# Sheet2.net
KiCad netlist of a schematic drawn in Altium Designer
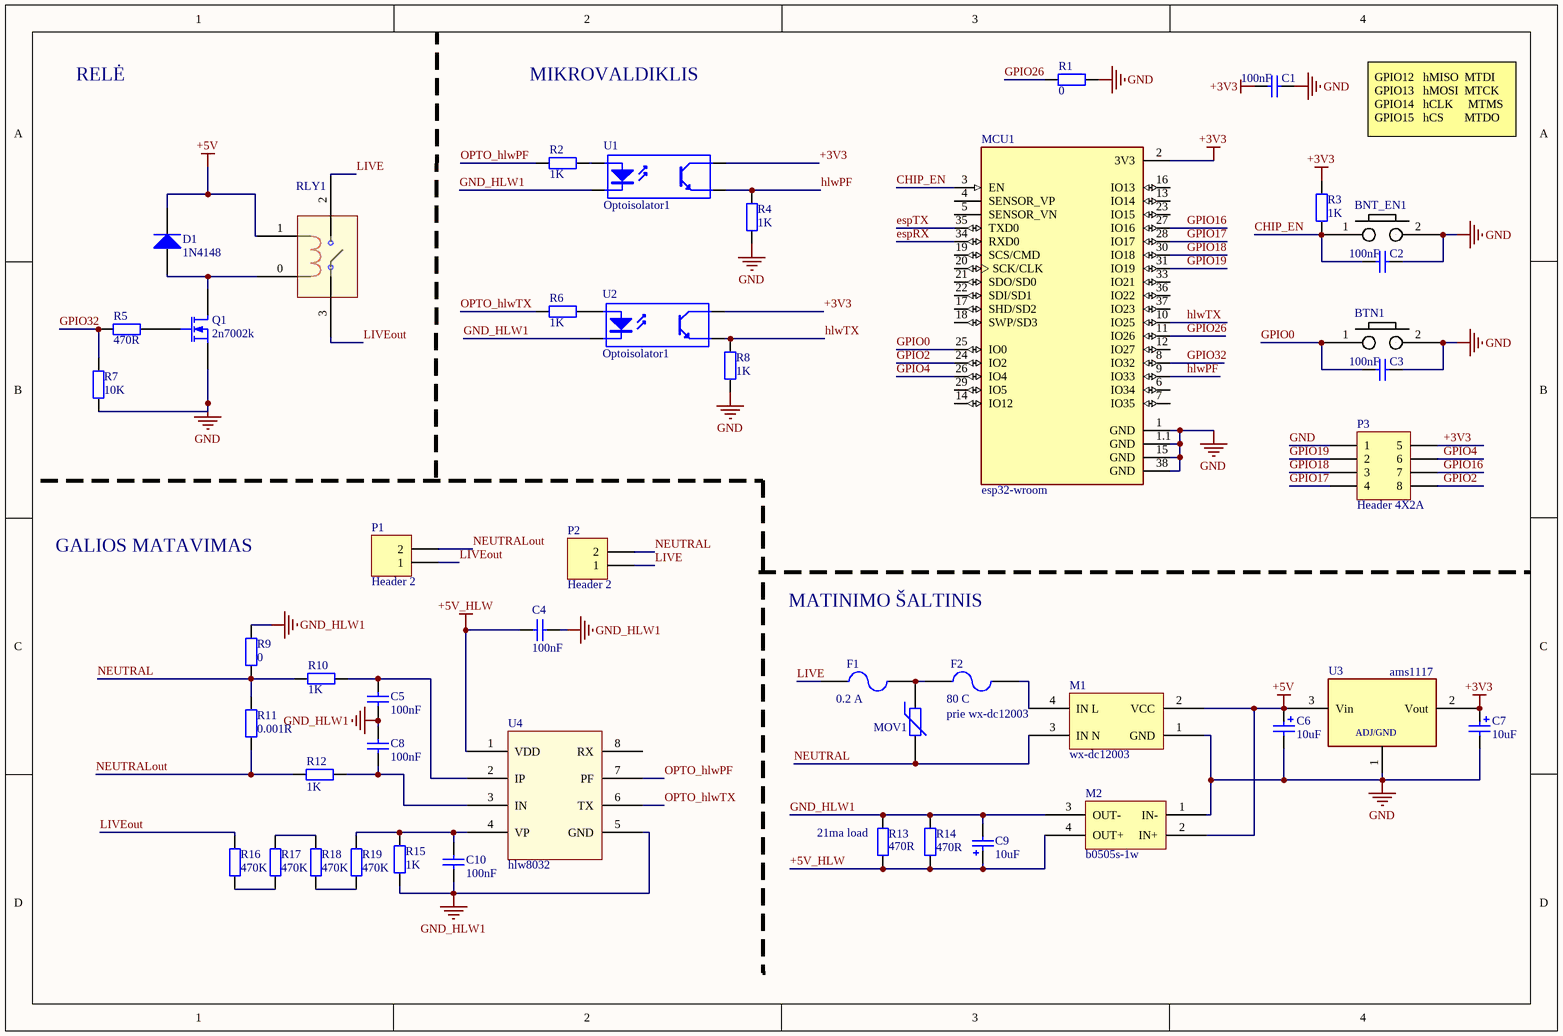
[diagram p0: Sheet2.SchDoc]

(export (version "E")
  (design (tool "Eeschema 10.0.6"))
  (components
    (comp (ref "BNT_EN1") (value "BTN") (footprint "BUTTON") (libsource (lib "Schlib1") (part "BTN")))
    (comp (ref "BTN1") (value "BTN") (footprint "BUTTON") (libsource (lib "Schlib1") (part "BTN")))
    (comp (ref "C1")
      (value "100nF")
      (footprint "1206 cap")
      (description "Capacitor (Semiconductor SIM Model)")
      (fields (field (name "Comment") "Cap Semi") (field (name "PUBLISHER") "Altium Limited"))
      (libsource (lib "Miscellaneous Devices") (part "Cap Semi"))
    )
    (comp (ref "C2")
      (value "100nF")
      (footprint "1206 cap")
      (description "Capacitor (Semiconductor SIM Model)")
      (fields (field (name "Comment") "Cap Semi") (field (name "PUBLISHER") "Altium Limited"))
      (libsource (lib "Miscellaneous Devices") (part "Cap Semi"))
    )
    (comp (ref "C3")
      (value "100nF")
      (footprint "1206 cap")
      (description "Capacitor (Semiconductor SIM Model)")
      (fields (field (name "Comment") "Cap Semi") (field (name "PUBLISHER") "Altium Limited"))
      (libsource (lib "Miscellaneous Devices") (part "Cap Semi"))
    )
    (comp (ref "C4")
      (value "100nF")
      (footprint "1206 cap")
      (description "Capacitor (Semiconductor SIM Model)")
      (fields (field (name "Comment") "Cap Semi") (field (name "PUBLISHER") "Altium Limited"))
      (libsource (lib "Miscellaneous Devices") (part "Cap Semi"))
    )
    (comp (ref "C5")
      (value "100nF")
      (footprint "1206 cap")
      (description "Capacitor (Semiconductor SIM Model)")
      (fields (field (name "Comment") "Cap Semi") (field (name "PUBLISHER") "Altium Limited"))
      (libsource (lib "Miscellaneous Devices") (part "Cap Semi"))
    )
    (comp (ref "C6")
      (value "10uF")
      (footprint "2312 cap tant")
      (description "Polarized Capacitor (Axial)")
      (fields (field (name "Comment") "Cap Pol2") (field (name "PUBLISHER") "Altium Limited"))
      (libsource (lib "Miscellaneous Devices") (part "Cap Pol2"))
    )
    (comp (ref "C7")
      (value "10uF")
      (footprint "2312 cap tant")
      (description "Polarized Capacitor (Axial)")
      (fields (field (name "Comment") "Cap Pol2") (field (name "PUBLISHER") "Altium Limited"))
      (libsource (lib "Miscellaneous Devices") (part "Cap Pol2"))
    )
    (comp (ref "C8")
      (value "100nF")
      (footprint "1206 cap")
      (description "Capacitor (Semiconductor SIM Model)")
      (fields (field (name "Comment") "Cap Semi") (field (name "PUBLISHER") "Altium Limited"))
      (libsource (lib "Miscellaneous Devices") (part "Cap Semi"))
    )
    (comp (ref "C9")
      (value "10uF")
      (footprint "2312 cap tant")
      (description "Polarized Capacitor (Axial)")
      (fields (field (name "Comment") "Cap Pol2") (field (name "PUBLISHER") "Altium Limited"))
      (libsource (lib "Miscellaneous Devices") (part "Cap Pol2"))
    )
    (comp (ref "C10")
      (value "100nF")
      (footprint "1206 cap")
      (description "Capacitor (Semiconductor SIM Model)")
      (fields (field (name "Comment") "Cap Semi") (field (name "PUBLISHER") "Altium Limited"))
      (libsource (lib "Miscellaneous Devices") (part "Cap Semi"))
    )
    (comp (ref "D1")
      (value "1N4148")
      (footprint "DO214-AC")
      (description "High Conductance Fast Diode")
      (fields (field (name "PUBLISHER") "Altium Limited"))
      (libsource (lib "Miscellaneous Devices") (part "Diode 1N4148"))
    )
    (comp (ref "F1")
      (value "0.2 A")
      (footprint "Fuse holder mini")
      (description "Fuse")
      (fields (field (name "PUBLISHER") "Altium Limited"))
      (libsource (lib "Miscellaneous Devices") (part "Fuse 2"))
    )
    (comp (ref "F2")
      (value "80 C")
      (footprint "PIN2")
      (description "Fuse")
      (fields (field (name "PUBLISHER") "Altium Limited"))
      (libsource (lib "Miscellaneous Devices") (part "Fuse 2"))
    )
    (comp (ref "M1")
      (value "wx-dc12003")
      (footprint "wx-dc12003_horiz")
      (libsource (lib "Schlib1") (part "wx-dc12003"))
    )
    (comp (ref "M2") (value "b0505s-1w") (footprint "B0505S") (libsource (lib "Schlib1") (part "b0505s-1w")))
    (comp (ref "MCU1")
      (value "esp32-wroom")
      (footprint "esp32-wroom")
      (libsource (lib "Schlib1") (part "esp32-wroom"))
    )
    (comp (ref "MOV1")
      (value "Res Varistor")
      (footprint "s20k250")
      (description "Varistor (Voltage-Sensitive Resistor)")
      (fields (field (name "PUBLISHER") "Altium Limited"))
      (libsource (lib "Miscellaneous Devices") (part "Res Varistor"))
    )
    (comp (ref "P1")
      (value "Header 2")
      (footprint "KF301-2P")
      (description "Header, 2-Pin")
      (fields (field (name "PUBLISHER") "Altium Limited"))
      (libsource (lib "Miscellaneous Connectors") (part "Header 2"))
    )
    (comp (ref "P2")
      (value "Header 2")
      (footprint "KF301-2P")
      (description "Header, 2-Pin")
      (fields (field (name "PUBLISHER") "Altium Limited"))
      (libsource (lib "Miscellaneous Connectors") (part "Header 2"))
    )
    (comp (ref "P3")
      (value "Header 4X2A")
      (footprint "HDR2X4_CEN")
      (description "Header, 4-Pin, Dual row")
      (fields (field (name "PUBLISHER") "Altium Limited"))
      (libsource (lib "Miscellaneous Connectors") (part "Header 4X2A"))
    )
    (comp (ref "Q1")
      (value "2n7002k")
      (footprint "SOT23")
      (description "N-Channel MOSFET")
      (fields (field (name "PUBLISHER") "Altium Limited"))
      (libsource (lib "Miscellaneous Devices") (part "MOSFET-N"))
    )
    (comp (ref "R1")
      (value "0")
      (footprint "0805 res")
      (description "Resistor")
      (fields (field (name "Comment") "Res2") (field (name "PUBLISHER") "Altium Limited"))
      (libsource (lib "") (part "Res2_2"))
    )
    (comp (ref "R2")
      (value "1K")
      (footprint "0805 res")
      (description "Resistor")
      (fields (field (name "Comment") "Res2") (field (name "PUBLISHER") "Altium Limited"))
      (libsource (lib "") (part "Res2_1"))
    )
    (comp (ref "R3")
      (value "1K")
      (footprint "0805 res")
      (description "Resistor")
      (fields (field (name "Comment") "Res2") (field (name "PUBLISHER") "Altium Limited"))
      (libsource (lib "Miscellaneous Devices") (part "Res2"))
    )
    (comp (ref "R4")
      (value "1K")
      (footprint "0805 res")
      (description "Resistor")
      (fields (field (name "Comment") "Res2") (field (name "PUBLISHER") "Altium Limited"))
      (libsource (lib "Miscellaneous Devices") (part "Res2"))
    )
    (comp (ref "R5")
      (value "470R")
      (footprint "0805 res")
      (description "Resistor")
      (fields (field (name "Comment") "Res2") (field (name "PUBLISHER") "Altium Limited"))
      (libsource (lib "") (part "Res2_2"))
    )
    (comp (ref "R6")
      (value "1K")
      (footprint "0805 res")
      (description "Resistor")
      (fields (field (name "Comment") "Res2") (field (name "PUBLISHER") "Altium Limited"))
      (libsource (lib "") (part "Res2_1"))
    )
    (comp (ref "R7")
      (value "10K")
      (footprint "0805 res")
      (description "Resistor")
      (fields (field (name "Comment") "Res2") (field (name "PUBLISHER") "Altium Limited"))
      (libsource (lib "") (part "Res2_3"))
    )
    (comp (ref "R8")
      (value "1K")
      (footprint "0805 res")
      (description "Resistor")
      (fields (field (name "Comment") "Res2") (field (name "PUBLISHER") "Altium Limited"))
      (libsource (lib "Miscellaneous Devices") (part "Res2"))
    )
    (comp (ref "R9")
      (value "0")
      (footprint "0805 res")
      (description "Resistor")
      (fields (field (name "Comment") "Res2") (field (name "PUBLISHER") "Altium Limited"))
      (libsource (lib "Miscellaneous Devices") (part "Res2"))
    )
    (comp (ref "R10")
      (value "1K")
      (footprint "0805 res")
      (description "Resistor")
      (fields (field (name "Comment") "Res2") (field (name "PUBLISHER") "Altium Limited"))
      (libsource (lib "") (part "Res2_1"))
    )
    (comp (ref "R11")
      (value "0.001R")
      (footprint "2512 res")
      (description "Resistor")
      (fields (field (name "Comment") "Res2") (field (name "PUBLISHER") "Altium Limited"))
      (libsource (lib "") (part "Res2_3"))
    )
    (comp (ref "R12")
      (value "1K")
      (footprint "0805 res")
      (description "Resistor")
      (fields (field (name "Comment") "Res2") (field (name "PUBLISHER") "Altium Limited"))
      (libsource (lib "") (part "Res2_1"))
    )
    (comp (ref "R13")
      (value "21ma load")
      (footprint "0805 res")
      (description "20ma minimum load resistor")
      (fields (field (name "ALTIUM_VALUE") "470R") (field (name "PUBLISHER") "Altium Limited"))
      (libsource (lib "Miscellaneous Devices") (part "Res2"))
    )
    (comp (ref "R14")
      (value "470R")
      (footprint "0805 res")
      (description "Resistor")
      (fields (field (name "Comment") "Res2") (field (name "PUBLISHER") "Altium Limited"))
      (libsource (lib "Miscellaneous Devices") (part "Res2"))
    )
    (comp (ref "R15")
      (value "1K")
      (footprint "0805 res")
      (description "Resistor")
      (fields (field (name "Comment") "Res2") (field (name "PUBLISHER") "Altium Limited"))
      (libsource (lib "Miscellaneous Devices") (part "Res2"))
    )
    (comp (ref "R16")
      (value "470K")
      (footprint "0805 res")
      (description "Resistor")
      (fields (field (name "Comment") "Res2") (field (name "PUBLISHER") "Altium Limited"))
      (libsource (lib "Miscellaneous Devices") (part "Res2"))
    )
    (comp (ref "R17")
      (value "470K")
      (footprint "0805 res")
      (description "Resistor")
      (fields (field (name "Comment") "Res2") (field (name "PUBLISHER") "Altium Limited"))
      (libsource (lib "Miscellaneous Devices") (part "Res2"))
    )
    (comp (ref "R18")
      (value "470K")
      (footprint "0805 res")
      (description "Resistor")
      (fields (field (name "Comment") "Res2") (field (name "PUBLISHER") "Altium Limited"))
      (libsource (lib "Miscellaneous Devices") (part "Res2"))
    )
    (comp (ref "R19")
      (value "470K")
      (footprint "0805 res")
      (description "Resistor")
      (fields (field (name "Comment") "Res2") (field (name "PUBLISHER") "Altium Limited"))
      (libsource (lib "Miscellaneous Devices") (part "Res2"))
    )
    (comp (ref "RLY1")
      (value "relay")
      (footprint "SMIH-05VDC-SL-A")
      (libsource (lib "Schlib1") (part "relay"))
    )
    (comp (ref "U1")
      (value "Optoisolator1")
      (footprint "PC817-smd")
      (description "4-Pin Phototransistor Optocoupler")
      (fields (field (name "PUBLISHER") "Altium Limited"))
      (libsource (lib "Miscellaneous Devices") (part "Optoisolator1"))
    )
    (comp (ref "U2")
      (value "Optoisolator1")
      (footprint "PC817-smd")
      (description "4-Pin Phototransistor Optocoupler")
      (fields (field (name "PUBLISHER") "Altium Limited"))
      (libsource (lib "Miscellaneous Devices") (part "Optoisolator1"))
    )
    (comp (ref "U3") (value "ams1117") (footprint "ams1117") (libsource (lib "Schlib1") (part "ams1117")))
    (comp (ref "U4") (value "hlw8032") (footprint "hlw8032") (libsource (lib "Schlib1") (part "hlw8032")))
  )
  (nets
    (net (code "1") (name "+3V3") (class "Default")
      (node (ref "C1") (pin "1") (pinfunction "1_1") (pintype "passive"))
      (node (ref "C7") (pin "1") (pinfunction "1_1") (pintype "passive"))
      (node (ref "MCU1") (pin "2") (pinfunction "3V3_2") (pintype "power_in"))
      (node (ref "P3") (pin "5") (pinfunction "5_5") (pintype "passive"))
      (node (ref "R3") (pin "1") (pinfunction "1_1") (pintype "passive"))
      (node (ref "U1") (pin "4") (pinfunction "C_4") (pintype "passive"))
      (node (ref "U2") (pin "4") (pinfunction "C_4") (pintype "passive"))
      (node (ref "U3") (pin "2") (pinfunction "Vout_2") (pintype "passive"))
    )
    (net (code "2") (name "+5V") (class "Default")
      (node (ref "C6") (pin "1") (pinfunction "1_1") (pintype "passive"))
      (node (ref "D1") (pin "2") (pinfunction "K_2") (pintype "passive"))
      (node (ref "M1") (pin "2") (pinfunction "VCC_2") (pintype "power_in"))
      (node (ref "M2") (pin "2") (pinfunction "IN+_2") (pintype "passive"))
      (node (ref "RLY1") (pin "1") (pinfunction "1_1") (pintype "passive"))
      (node (ref "U3") (pin "3") (pinfunction "Vin_3") (pintype "passive"))
    )
    (net (code "3") (name "+5V_HLW") (class "Default")
      (node (ref "C4") (pin "1") (pinfunction "1_1") (pintype "passive"))
      (node (ref "C9") (pin "1") (pinfunction "1_1") (pintype "passive"))
      (node (ref "M2") (pin "4") (pinfunction "OUT+_4") (pintype "passive"))
      (node (ref "R13") (pin "2") (pinfunction "2_2") (pintype "passive"))
      (node (ref "R14") (pin "2") (pinfunction "2_2") (pintype "passive"))
      (node (ref "U4") (pin "1") (pinfunction "VDD_1") (pintype "passive"))
    )
    (net (code "4") (name "/CHIP_EN") (class "Default")
      (node (ref "BNT_EN1") (pin "1") (pinfunction "1_1") (pintype "passive"))
      (node (ref "C2") (pin "1") (pinfunction "1_1") (pintype "passive"))
      (node (ref "MCU1") (pin "3") (pinfunction "EN_3") (pintype "input"))
      (node (ref "R3") (pin "2") (pinfunction "2_2") (pintype "passive"))
    )
    (net (code "5") (name "/GPIO0") (class "Default")
      (node (ref "BTN1") (pin "1") (pinfunction "1_1") (pintype "passive"))
      (node (ref "C3") (pin "1") (pinfunction "1_1") (pintype "passive"))
      (node (ref "MCU1") (pin "25") (pinfunction "IO0_25") (pintype "bidirectional"))
    )
    (net (code "6") (name "/GPIO2") (class "Default")
      (node (ref "MCU1") (pin "24") (pinfunction "IO2_24") (pintype "bidirectional"))
      (node (ref "P3") (pin "8") (pinfunction "8_8") (pintype "passive"))
    )
    (net (code "7") (name "/GPIO4") (class "Default")
      (node (ref "MCU1") (pin "26") (pinfunction "IO4_26") (pintype "bidirectional"))
      (node (ref "P3") (pin "6") (pinfunction "6_6") (pintype "passive"))
    )
    (net (code "8") (name "/GPIO16") (class "Default")
      (node (ref "MCU1") (pin "27") (pinfunction "IO16_27") (pintype "bidirectional"))
      (node (ref "P3") (pin "7") (pinfunction "7_7") (pintype "passive"))
    )
    (net (code "9") (name "/GPIO17") (class "Default")
      (node (ref "MCU1") (pin "28") (pinfunction "IO17_28") (pintype "bidirectional"))
      (node (ref "P3") (pin "4") (pinfunction "4_4") (pintype "passive"))
    )
    (net (code "10") (name "/GPIO18") (class "Default")
      (node (ref "MCU1") (pin "30") (pinfunction "IO18_30") (pintype "bidirectional"))
      (node (ref "P3") (pin "3") (pinfunction "3_3") (pintype "passive"))
    )
    (net (code "11") (name "/GPIO19") (class "Default")
      (node (ref "MCU1") (pin "31") (pinfunction "IO19_31") (pintype "bidirectional"))
      (node (ref "P3") (pin "2") (pinfunction "2_2") (pintype "passive"))
    )
    (net (code "12") (name "/GPIO26") (class "Default")
      (node (ref "MCU1") (pin "11") (pinfunction "IO26_11") (pintype "bidirectional"))
      (node (ref "R1") (pin "1") (pinfunction "1_1") (pintype "passive"))
    )
    (net (code "13") (name "/GPIO32") (class "Default")
      (node (ref "MCU1") (pin "8") (pinfunction "IO32_8") (pintype "bidirectional"))
      (node (ref "R5") (pin "1") (pinfunction "1_1") (pintype "passive"))
      (node (ref "R7") (pin "2") (pinfunction "2_2") (pintype "passive"))
    )
    (net (code "14") (name "/LIVE") (class "Default")
      (node (ref "F1") (pin "1") (pinfunction "1_1") (pintype "passive"))
      (node (ref "P2") (pin "1") (pinfunction "1_1") (pintype "passive"))
      (node (ref "RLY1") (pin "2") (pinfunction "2_2") (pintype "power_in"))
    )
    (net (code "15") (name "/LIVEout") (class "Default")
      (node (ref "P1") (pin "1") (pinfunction "1_1") (pintype "passive"))
      (node (ref "R16") (pin "1") (pinfunction "1_1") (pintype "passive"))
      (node (ref "RLY1") (pin "3") (pinfunction "3_3") (pintype "power_in"))
    )
    (net (code "16") (name "/NEUTRAL") (class "Default")
      (node (ref "M1") (pin "3") (pinfunction "IN_N_3") (pintype "power_in"))
      (node (ref "MOV1") (pin "2") (pinfunction "2_2") (pintype "passive"))
      (node (ref "P2") (pin "2") (pinfunction "2_2") (pintype "passive"))
      (node (ref "R10") (pin "2") (pinfunction "2_2") (pintype "passive"))
      (node (ref "R11") (pin "2") (pinfunction "2_2") (pintype "passive"))
      (node (ref "R9") (pin "2") (pinfunction "2_2") (pintype "passive"))
    )
    (net (code "17") (name "/NEUTRALout") (class "Default")
      (node (ref "P1") (pin "2") (pinfunction "2_2") (pintype "passive"))
      (node (ref "R11") (pin "1") (pinfunction "1_1") (pintype "passive"))
      (node (ref "R12") (pin "2") (pinfunction "2_2") (pintype "passive"))
    )
    (net (code "18") (name "/OPTO_hlwPF") (class "Default")
      (node (ref "R2") (pin "2") (pinfunction "2_2") (pintype "passive"))
      (node (ref "U4") (pin "7") (pinfunction "PF_7") (pintype "passive"))
    )
    (net (code "19") (name "/OPTO_hlwTX") (class "Default")
      (node (ref "R6") (pin "2") (pinfunction "2_2") (pintype "passive"))
      (node (ref "U4") (pin "6") (pinfunction "TX_6") (pintype "passive"))
    )
    (net (code "20") (name "/espRX") (class "Default")
      (node (ref "MCU1") (pin "34") (pinfunction "RXD0_34") (pintype "bidirectional"))
    )
    (net (code "21") (name "/espTX") (class "Default")
      (node (ref "MCU1") (pin "35") (pinfunction "TXD0_35") (pintype "bidirectional"))
    )
    (net (code "22") (name "/hlwPF") (class "Default")
      (node (ref "MCU1") (pin "9") (pinfunction "IO33_9") (pintype "bidirectional"))
      (node (ref "R4") (pin "1") (pinfunction "1_1") (pintype "passive"))
      (node (ref "U1") (pin "3") (pinfunction "E_3") (pintype "passive"))
    )
    (net (code "23") (name "/hlwTX") (class "Default")
      (node (ref "MCU1") (pin "10") (pinfunction "IO25_10") (pintype "bidirectional"))
      (node (ref "R8") (pin "1") (pinfunction "1_1") (pintype "passive"))
      (node (ref "U2") (pin "3") (pinfunction "E_3") (pintype "passive"))
    )
    (net (code "24") (name "GND") (class "Default")
      (node (ref "BNT_EN1") (pin "2") (pinfunction "2_2") (pintype "passive"))
      (node (ref "BTN1") (pin "2") (pinfunction "2_2") (pintype "passive"))
      (node (ref "C1") (pin "2") (pinfunction "2_2") (pintype "passive"))
      (node (ref "C2") (pin "2") (pinfunction "2_2") (pintype "passive"))
      (node (ref "C3") (pin "2") (pinfunction "2_2") (pintype "passive"))
      (node (ref "C6") (pin "2") (pinfunction "2_2") (pintype "passive"))
      (node (ref "C7") (pin "2") (pinfunction "2_2") (pintype "passive"))
      (node (ref "M1") (pin "1") (pinfunction "GND_1") (pintype "power_in"))
      (node (ref "M2") (pin "1") (pinfunction "IN-_1") (pintype "passive"))
      (node (ref "MCU1") (pin "1") (pinfunction "GND_1") (pintype "power_in"))
      (node (ref "MCU1") (pin "1.1") (pinfunction "GND_1.1") (pintype "power_in"))
      (node (ref "MCU1") (pin "15") (pinfunction "GND_15") (pintype "power_in"))
      (node (ref "MCU1") (pin "38") (pinfunction "GND_38") (pintype "power_in"))
      (node (ref "P3") (pin "1") (pinfunction "1_1") (pintype "passive"))
      (node (ref "Q1") (pin "3") (pinfunction "S_3") (pintype "passive"))
      (node (ref "R1") (pin "2") (pinfunction "2_2") (pintype "passive"))
      (node (ref "R4") (pin "2") (pinfunction "2_2") (pintype "passive"))
      (node (ref "R7") (pin "1") (pinfunction "1_1") (pintype "passive"))
      (node (ref "R8") (pin "2") (pinfunction "2_2") (pintype "passive"))
      (node (ref "U3") (pin "1") (pinfunction "ADJ/GND_1") (pintype "power_in"))
    )
    (net (code "25") (name "GND_HLW1") (class "Default")
      (node (ref "C10") (pin "1") (pinfunction "1_1") (pintype "passive"))
      (node (ref "C4") (pin "2") (pinfunction "2_2") (pintype "passive"))
      (node (ref "C5") (pin "2") (pinfunction "2_2") (pintype "passive"))
      (node (ref "C8") (pin "1") (pinfunction "1_1") (pintype "passive"))
      (node (ref "C9") (pin "2") (pinfunction "2_2") (pintype "passive"))
      (node (ref "M2") (pin "3") (pinfunction "OUT-_3") (pintype "passive"))
      (node (ref "R13") (pin "1") (pinfunction "1_1") (pintype "passive"))
      (node (ref "R14") (pin "1") (pinfunction "1_1") (pintype "passive"))
      (node (ref "R15") (pin "2") (pinfunction "2_2") (pintype "passive"))
      (node (ref "R9") (pin "1") (pinfunction "1_1") (pintype "passive"))
      (node (ref "U1") (pin "2") (pinfunction "K_2") (pintype "passive"))
      (node (ref "U2") (pin "2") (pinfunction "K_2") (pintype "passive"))
      (node (ref "U4") (pin "5") (pinfunction "GND_5") (pintype "passive"))
    )
    (net (code "26") (name "Net-(D1-A)") (class "Default")
      (node (ref "D1") (pin "1") (pinfunction "A_1") (pintype "passive"))
      (node (ref "Q1") (pin "1") (pinfunction "D_1") (pintype "passive"))
      (node (ref "RLY1") (pin "0") (pinfunction "0_0") (pintype "passive"))
    )
    (net (code "27") (name "Net-(F1-Pad2)") (class "Default")
      (node (ref "F1") (pin "2") (pinfunction "2_2") (pintype "passive"))
      (node (ref "F2") (pin "1") (pinfunction "1_1") (pintype "passive"))
      (node (ref "MOV1") (pin "1") (pinfunction "1_1") (pintype "passive"))
    )
    (net (code "28") (name "Net-(M1-IN_L)") (class "Default")
      (node (ref "F2") (pin "2") (pinfunction "2_2") (pintype "passive"))
      (node (ref "M1") (pin "4") (pinfunction "IN_L_4") (pintype "power_in"))
    )
    (net (code "29") (name "Net-(Q1-G)") (class "Default")
      (node (ref "Q1") (pin "2") (pinfunction "G_2") (pintype "passive"))
      (node (ref "R5") (pin "2") (pinfunction "2_2") (pintype "passive"))
    )
    (net (code "30") (name "Net-(R16-Pad2)") (class "Default")
      (node (ref "R16") (pin "2") (pinfunction "2_2") (pintype "passive"))
      (node (ref "R17") (pin "2") (pinfunction "2_2") (pintype "passive"))
    )
    (net (code "31") (name "Net-(R17-Pad1)") (class "Default")
      (node (ref "R17") (pin "1") (pinfunction "1_1") (pintype "passive"))
      (node (ref "R18") (pin "1") (pinfunction "1_1") (pintype "passive"))
    )
    (net (code "32") (name "Net-(R18-Pad2)") (class "Default")
      (node (ref "R18") (pin "2") (pinfunction "2_2") (pintype "passive"))
      (node (ref "R19") (pin "2") (pinfunction "2_2") (pintype "passive"))
    )
    (net (code "33") (name "Net-(U1-A)") (class "Default")
      (node (ref "R2") (pin "1") (pinfunction "1_1") (pintype "passive"))
      (node (ref "U1") (pin "1") (pinfunction "A_1") (pintype "passive"))
    )
    (net (code "34") (name "Net-(U2-A)") (class "Default")
      (node (ref "R6") (pin "1") (pinfunction "1_1") (pintype "passive"))
      (node (ref "U2") (pin "1") (pinfunction "A_1") (pintype "passive"))
    )
    (net (code "35") (name "Net-(U4-IN)") (class "Default")
      (node (ref "C8") (pin "2") (pinfunction "2_2") (pintype "passive"))
      (node (ref "R12") (pin "1") (pinfunction "1_1") (pintype "passive"))
      (node (ref "U4") (pin "3") (pinfunction "IN_3") (pintype "passive"))
    )
    (net (code "36") (name "Net-(U4-IP)") (class "Default")
      (node (ref "C5") (pin "1") (pinfunction "1_1") (pintype "passive"))
      (node (ref "R10") (pin "1") (pinfunction "1_1") (pintype "passive"))
      (node (ref "U4") (pin "2") (pinfunction "IP_2") (pintype "passive"))
    )
    (net (code "37") (name "Net-(U4-VP)") (class "Default")
      (node (ref "C10") (pin "2") (pinfunction "2_2") (pintype "passive"))
      (node (ref "R15") (pin "1") (pinfunction "1_1") (pintype "passive"))
      (node (ref "R19") (pin "1") (pinfunction "1_1") (pintype "passive"))
      (node (ref "U4") (pin "4") (pinfunction "VP_4") (pintype "passive"))
    )
    (net (code "38") (name "unconnected-(MCU1-IO5-Pad29)") (class "Default")
      (node (ref "MCU1") (pin "29") (pinfunction "IO5_29") (pintype "bidirectional"))
    )
    (net (code "39") (name "unconnected-(MCU1-IO12-Pad14)") (class "Default")
      (node (ref "MCU1") (pin "14") (pinfunction "IO12_14") (pintype "bidirectional"))
    )
    (net (code "40") (name "unconnected-(MCU1-IO13-Pad16)") (class "Default")
      (node (ref "MCU1") (pin "16") (pinfunction "IO13_16") (pintype "bidirectional"))
    )
    (net (code "41") (name "unconnected-(MCU1-IO14-Pad13)") (class "Default")
      (node (ref "MCU1") (pin "13") (pinfunction "IO14_13") (pintype "bidirectional"))
    )
    (net (code "42") (name "unconnected-(MCU1-IO15-Pad23)") (class "Default")
      (node (ref "MCU1") (pin "23") (pinfunction "IO15_23") (pintype "bidirectional"))
    )
    (net (code "43") (name "unconnected-(MCU1-IO21-Pad33)") (class "Default")
      (node (ref "MCU1") (pin "33") (pinfunction "IO21_33") (pintype "bidirectional"))
    )
    (net (code "44") (name "unconnected-(MCU1-IO22-Pad36)") (class "Default")
      (node (ref "MCU1") (pin "36") (pinfunction "IO22_36") (pintype "bidirectional"))
    )
    (net (code "45") (name "unconnected-(MCU1-IO23-Pad37)") (class "Default")
      (node (ref "MCU1") (pin "37") (pinfunction "IO23_37") (pintype "bidirectional"))
    )
    (net (code "46") (name "unconnected-(MCU1-IO27-Pad12)") (class "Default")
      (node (ref "MCU1") (pin "12") (pinfunction "IO27_12") (pintype "bidirectional"))
    )
    (net (code "47") (name "unconnected-(MCU1-IO34-Pad6)") (class "Default")
      (node (ref "MCU1") (pin "6") (pinfunction "IO34_6") (pintype "bidirectional"))
    )
    (net (code "48") (name "unconnected-(MCU1-IO35-Pad7)") (class "Default")
      (node (ref "MCU1") (pin "7") (pinfunction "IO35_7") (pintype "bidirectional"))
    )
    (net (code "49") (name "unconnected-(MCU1-SCK{slash}CLK-Pad20)") (class "Default")
      (node (ref "MCU1") (pin "20") (pinfunction "SCK/CLK_20") (pintype "bidirectional"))
    )
    (net (code "50") (name "unconnected-(MCU1-SCS{slash}CMD-Pad19)") (class "Default")
      (node (ref "MCU1") (pin "19") (pinfunction "SCS/CMD_19") (pintype "bidirectional"))
    )
    (net (code "51") (name "unconnected-(MCU1-SDI{slash}SD1-Pad22)") (class "Default")
      (node (ref "MCU1") (pin "22") (pinfunction "SDI/SD1_22") (pintype "bidirectional"))
    )
    (net (code "52") (name "unconnected-(MCU1-SDO{slash}SD0-Pad21)") (class "Default")
      (node (ref "MCU1") (pin "21") (pinfunction "SDO/SD0_21") (pintype "bidirectional"))
    )
    (net (code "53") (name "unconnected-(MCU1-SENSOR_VN-Pad5)") (class "Default")
      (node (ref "MCU1") (pin "5") (pinfunction "SENSOR_VN_5") (pintype "passive"))
    )
    (net (code "54") (name "unconnected-(MCU1-SENSOR_VP-Pad4)") (class "Default")
      (node (ref "MCU1") (pin "4") (pinfunction "SENSOR_VP_4") (pintype "passive"))
    )
    (net (code "55") (name "unconnected-(MCU1-SHD{slash}SD2-Pad17)") (class "Default")
      (node (ref "MCU1") (pin "17") (pinfunction "SHD/SD2_17") (pintype "bidirectional"))
    )
    (net (code "56") (name "unconnected-(MCU1-SWP{slash}SD3-Pad18)") (class "Default")
      (node (ref "MCU1") (pin "18") (pinfunction "SWP/SD3_18") (pintype "bidirectional"))
    )
    (net (code "57") (name "unconnected-(U4-RX-Pad8)") (class "Default")
      (node (ref "U4") (pin "8") (pinfunction "RX_8") (pintype "passive"))
    )
  )
)
